# mixtape.net
KiCad netlist of a schematic drawn in EAGLE
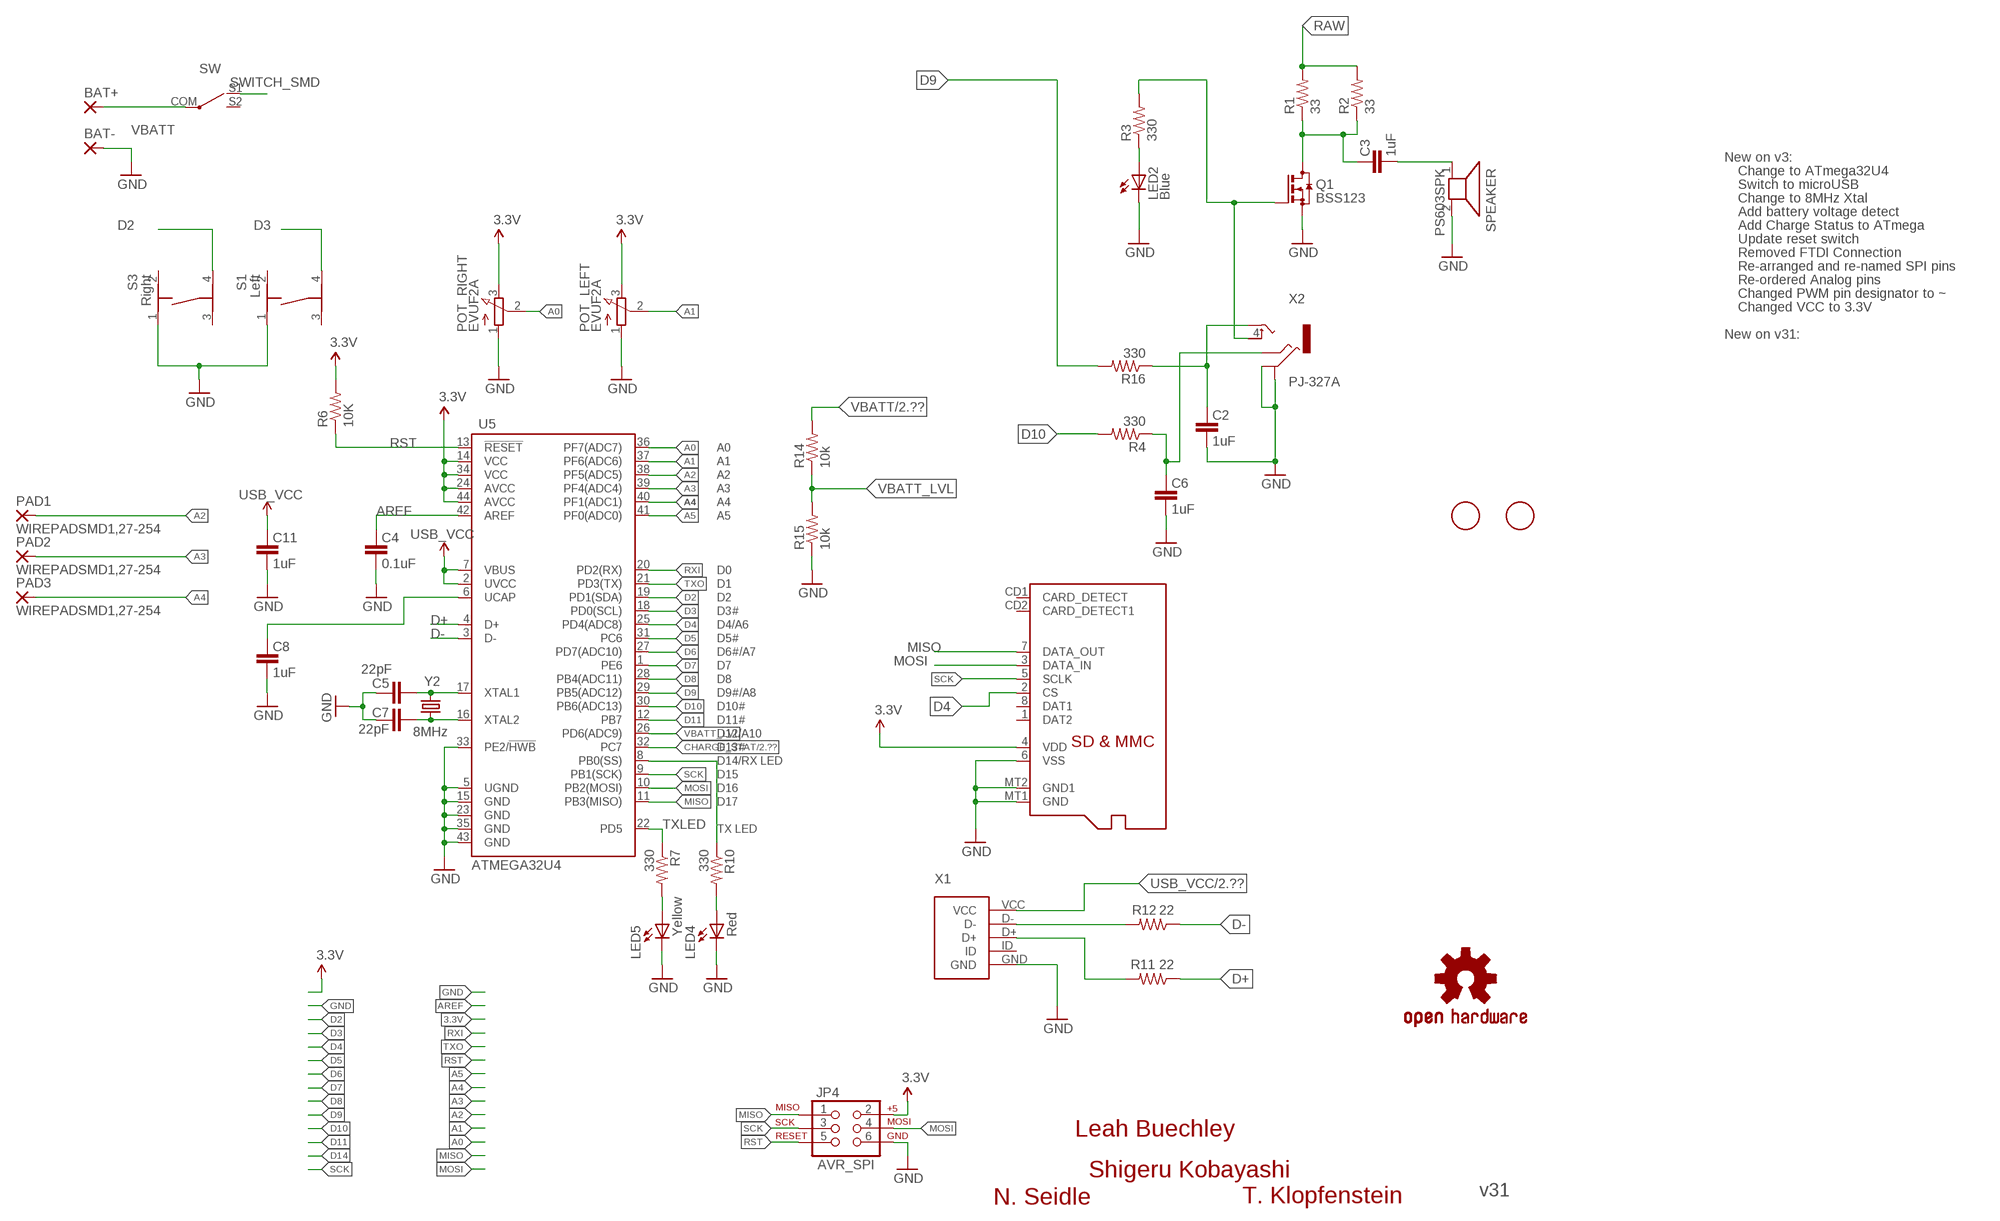
[diagram p0: schematic, sheet 1]
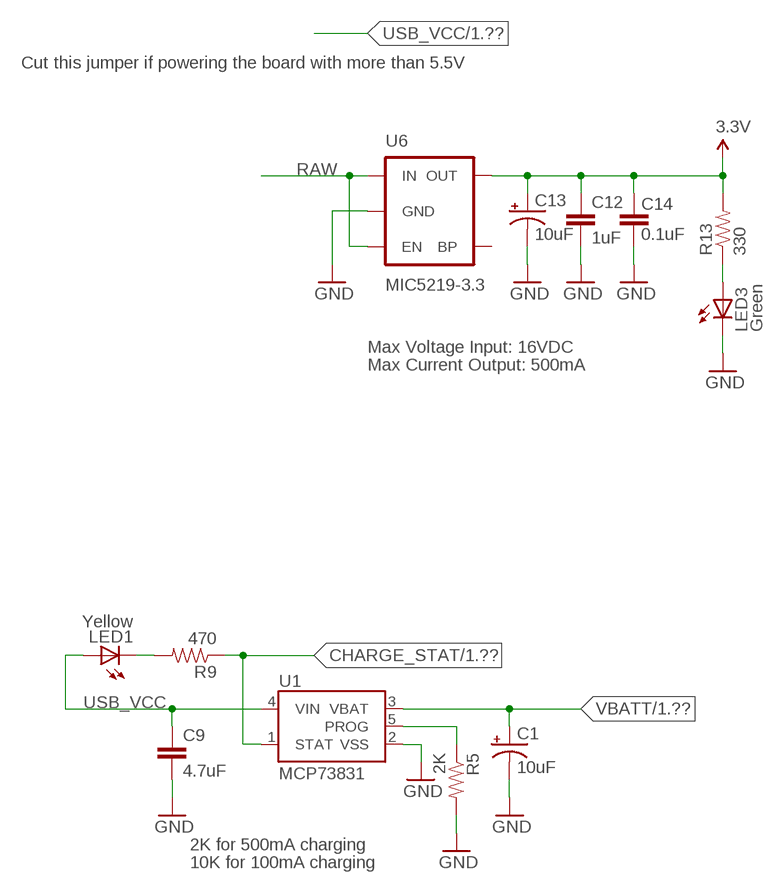
[diagram p1: schematic, sheet 2]

(export (version "E")
  (design (tool "Eeschema 10.0.6"))
  (components
    (comp (ref "C1")
      (value "10uF")
      (footprint "eagle-import:EIA3216")
      (libsource (lib "eagle-import") (part "CAP_POL1206"))
    )
    (comp (ref "C9")
      (value "4.7uF")
      (footprint "eagle-import:0603-CAP")
      (libsource (lib "eagle-import") (part "CAP0603-CAP"))
    )
    (comp (ref "C12")
      (value "1uF")
      (footprint "eagle-import:0603-CAP")
      (libsource (lib "eagle-import") (part "CAP0603-CAP"))
    )
    (comp (ref "C13")
      (value "10uF")
      (footprint "eagle-import:EIA3216")
      (libsource (lib "eagle-import") (part "CAP_POL1206"))
    )
    (comp (ref "C14")
      (value "0.1uF")
      (footprint "eagle-import:0603-CAP")
      (libsource (lib "eagle-import") (part "CAP0603-CAP"))
    )
    (comp (ref "LED1")
      (value "Yellow")
      (footprint "eagle-import:LED-0603")
      (libsource (lib "eagle-import") (part "LED0603"))
    )
    (comp (ref "LED3")
      (value "Green")
      (footprint "eagle-import:LED-0603")
      (libsource (lib "eagle-import") (part "LED0603"))
    )
    (comp (ref "R5")
      (value "2K")
      (footprint "eagle-import:0603-RES")
      (libsource (lib "eagle-import") (part "RESISTOR0603-RES"))
    )
    (comp (ref "R9")
      (value "470")
      (footprint "eagle-import:0603-RES")
      (libsource (lib "eagle-import") (part "RESISTOR0603-RES"))
    )
    (comp (ref "R13")
      (value "330")
      (footprint "eagle-import:0603-RES")
      (libsource (lib "eagle-import") (part "RESISTOR0603-RES"))
    )
    (comp (ref "U1")
      (value "MCP73831")
      (footprint "eagle-import:SOT23-5")
      (libsource (lib "eagle-import") (part "MCP73831"))
    )
    (comp (ref "U6")
      (value "MIC5219-3.3")
      (footprint "eagle-import:SOT23-5")
      (libsource (lib "eagle-import") (part "V_REG_LDOSMD"))
    )
    (comp (ref "BAT+")
      (value "SMD5")
      (footprint "eagle-import:SMD2,54-5,08")
      (libsource (lib "eagle-import") (part "SMD5"))
    )
    (comp (ref "BAT-")
      (value "SMD5")
      (footprint "eagle-import:SMD2,54-5,08")
      (libsource (lib "eagle-import") (part "SMD5"))
    )
    (comp (ref "C2")
      (value "1uF")
      (footprint "eagle-import:0603-CAP")
      (libsource (lib "eagle-import") (part "CAP0603-CAP"))
    )
    (comp (ref "C3")
      (value "1uF")
      (footprint "eagle-import:0603-CAP")
      (libsource (lib "eagle-import") (part "CAP0603-CAP"))
    )
    (comp (ref "C4")
      (value "0.1uF")
      (footprint "eagle-import:0603-CAP")
      (libsource (lib "eagle-import") (part "CAP0603-CAP"))
    )
    (comp (ref "C5")
      (value "22pF")
      (footprint "eagle-import:0603-CAP")
      (libsource (lib "eagle-import") (part "CAP0603-CAP"))
    )
    (comp (ref "C6")
      (value "1uF")
      (footprint "eagle-import:0603-CAP")
      (libsource (lib "eagle-import") (part "CAP0603-CAP"))
    )
    (comp (ref "C7")
      (value "22pF")
      (footprint "eagle-import:0603-CAP")
      (libsource (lib "eagle-import") (part "CAP0603-CAP"))
    )
    (comp (ref "C8")
      (value "1uF")
      (footprint "eagle-import:0603-CAP")
      (libsource (lib "eagle-import") (part "CAP0603-CAP"))
    )
    (comp (ref "C11")
      (value "1uF")
      (footprint "eagle-import:0603-CAP")
      (libsource (lib "eagle-import") (part "CAP0603-CAP"))
    )
    (comp (ref "JP4")
      (value "AVR_SPI")
      (footprint "eagle-import:2X3")
      (libsource (lib "eagle-import") (part "AVR_SPI_PRG_6PTH"))
    )
    (comp (ref "LED2")
      (value "Blue")
      (footprint "eagle-import:LED-0603")
      (libsource (lib "eagle-import") (part "LED0603"))
    )
    (comp (ref "LED4")
      (value "Red")
      (footprint "eagle-import:LED-0603")
      (libsource (lib "eagle-import") (part "LED0603"))
    )
    (comp (ref "LED5")
      (value "Yellow")
      (footprint "eagle-import:LED-0603")
      (libsource (lib "eagle-import") (part "LED0603"))
    )
    (comp (ref "LOGO1")
      (value "OSHW-LOGOL")
      (footprint "eagle-import:OSHW-LOGO-L")
      (libsource (lib "eagle-import") (part "OSHW-LOGOL"))
    )
    (comp (ref "PAD1")
      (value "WIREPADSMD1,27-254")
      (footprint "eagle-import:SMD1,27-2,54")
      (libsource (lib "eagle-import") (part "WIREPADSMD1,27-254"))
    )
    (comp (ref "PAD2")
      (value "WIREPADSMD1,27-254")
      (footprint "eagle-import:SMD1,27-2,54")
      (libsource (lib "eagle-import") (part "WIREPADSMD1,27-254"))
    )
    (comp (ref "PAD3")
      (value "WIREPADSMD1,27-254")
      (footprint "eagle-import:SMD1,27-2,54")
      (libsource (lib "eagle-import") (part "WIREPADSMD1,27-254"))
    )
    (comp (ref "POT_LEFT")
      (value "EVUF2A")
      (footprint "eagle-import:EVUF")
      (libsource (lib "eagle-import") (part "EVUAF2"))
    )
    (comp (ref "POT_RIGHT")
      (value "EVUF2A")
      (footprint "eagle-import:EVUF")
      (libsource (lib "eagle-import") (part "EVUAF2"))
    )
    (comp (ref "Q1")
      (value "BSS123")
      (footprint "eagle-import:SOT23")
      (libsource (lib "eagle-import") (part "BSS123"))
    )
    (comp (ref "R1")
      (value "33")
      (footprint "eagle-import:0603-RES")
      (libsource (lib "eagle-import") (part "RESISTOR0603-RES"))
    )
    (comp (ref "R2")
      (value "33")
      (footprint "eagle-import:0603-RES")
      (libsource (lib "eagle-import") (part "RESISTOR0603-RES"))
    )
    (comp (ref "R3")
      (value "330")
      (footprint "eagle-import:0603-RES")
      (libsource (lib "eagle-import") (part "RESISTOR0603-RES"))
    )
    (comp (ref "R4")
      (value "330")
      (footprint "eagle-import:0603-RES")
      (libsource (lib "eagle-import") (part "RESISTOR0603-RES"))
    )
    (comp (ref "R6")
      (value "10K")
      (footprint "eagle-import:0603-RES")
      (libsource (lib "eagle-import") (part "RESISTOR0603-RES"))
    )
    (comp (ref "R7")
      (value "330")
      (footprint "eagle-import:0603-RES")
      (libsource (lib "eagle-import") (part "RESISTOR0603-RES"))
    )
    (comp (ref "R10")
      (value "330")
      (footprint "eagle-import:0603-RES")
      (libsource (lib "eagle-import") (part "RESISTOR0603-RES"))
    )
    (comp (ref "R11")
      (value "22")
      (footprint "eagle-import:0603-RES")
      (libsource (lib "eagle-import") (part "RESISTOR0603-RES"))
    )
    (comp (ref "R12")
      (value "22")
      (footprint "eagle-import:0603-RES")
      (libsource (lib "eagle-import") (part "RESISTOR0603-RES"))
    )
    (comp (ref "R14")
      (value "10k")
      (footprint "eagle-import:0603-RES")
      (libsource (lib "eagle-import") (part "RESISTOR0603-RES"))
    )
    (comp (ref "R15")
      (value "10k")
      (footprint "eagle-import:0603-RES")
      (libsource (lib "eagle-import") (part "RESISTOR0603-RES"))
    )
    (comp (ref "R16")
      (value "330")
      (footprint "eagle-import:0603-RES")
      (libsource (lib "eagle-import") (part "RESISTOR0603-RES"))
    )
    (comp (ref "S1")
      (value "Left")
      (footprint "eagle-import:TASTER-9314_SMD")
      (libsource (lib "eagle-import") (part "TASTER-9314_SMD"))
    )
    (comp (ref "S3")
      (value "Right")
      (footprint "eagle-import:TASTER-9314_SMD")
      (libsource (lib "eagle-import") (part "TASTER-9314_SMD"))
    )
    (comp (ref "SD")
      (value "MICROSD")
      (footprint "eagle-import:MICROSD")
      (libsource (lib "eagle-import") (part "MICROSD"))
    )
    (comp (ref "SPEAKER")
      (value "PS603SPK")
      (footprint "eagle-import:PS603")
      (libsource (lib "eagle-import") (part "PS603SPK"))
    )
    (comp (ref "SW")
      (value "SWITCH_SMD")
      (footprint "eagle-import:SWITCH_SMD")
      (libsource (lib "eagle-import") (part "SWITCH_SMD"))
    )
    (comp (ref "U$1")
      (value "FIDUCIAL")
      (footprint "eagle-import:FIDUCIAL_1MM")
      (libsource (lib "eagle-import") (part "FIDUCIAL"))
    )
    (comp (ref "U$2")
      (value "FIDUCIAL")
      (footprint "eagle-import:FIDUCIAL_1MM")
      (libsource (lib "eagle-import") (part "FIDUCIAL"))
    )
    (comp (ref "U5")
      (value "ATMEGA32U4")
      (footprint "eagle-import:QFN-44-NOPAD_1_1")
      (libsource (lib "eagle-import") (part "ATMEGA32U41{colon}1"))
    )
    (comp (ref "X1")
      (value "USB_B_SMD")
      (footprint "eagle-import:USB_B_SMD")
      (libsource (lib "eagle-import") (part "USB_B_SMD"))
    )
    (comp (ref "X2")
      (value "PJ-327A")
      (footprint "eagle-import:PJ-327A")
      (libsource (lib "eagle-import") (part "PJ-327A"))
    )
    (comp (ref "Y2")
      (value "8MHz")
      (footprint "eagle-import:CRYSTAL-SMD-5X3")
      (libsource (lib "eagle-import") (part "CRYSTAL5X3"))
    )
  )
  (nets
    (net (code "1") (name "3.3V") (class "Default")
      (node (ref "C12") (pin "1") (pinfunction "1_1") (pintype "passive"))
      (node (ref "C13") (pin "A") (pinfunction "+_A") (pintype "passive"))
      (node (ref "C14") (pin "2") (pinfunction "2_2") (pintype "passive"))
      (node (ref "JP4") (pin "2") (pinfunction "2_2") (pintype "passive"))
      (node (ref "POT_LEFT") (pin "3") (pinfunction "E_3") (pintype "passive"))
      (node (ref "POT_RIGHT") (pin "3") (pinfunction "E_3") (pintype "passive"))
      (node (ref "R13") (pin "2") (pinfunction "2_2") (pintype "passive"))
      (node (ref "R6") (pin "2") (pinfunction "2_2") (pintype "passive"))
      (node (ref "SD") (pin "4") (pinfunction "VDD_4") (pintype "power_in"))
      (node (ref "U5") (pin "14") (pinfunction "VCC_14") (pintype "bidirectional"))
      (node (ref "U5") (pin "24") (pinfunction "AVCC_24") (pintype "bidirectional"))
      (node (ref "U5") (pin "34") (pinfunction "VCC_34") (pintype "bidirectional"))
      (node (ref "U5") (pin "44") (pinfunction "AVCC_44") (pintype "bidirectional"))
      (node (ref "U6") (pin "5") (pinfunction "OUT_5") (pintype "passive"))
    )
    (net (code "2") (name "A0") (class "Default")
      (node (ref "POT_RIGHT") (pin "2") (pinfunction "S_2") (pintype "passive"))
      (node (ref "U5") (pin "36") (pinfunction "PF7(ADC7)_36") (pintype "bidirectional"))
    )
    (net (code "3") (name "A1") (class "Default")
      (node (ref "POT_LEFT") (pin "2") (pinfunction "S_2") (pintype "passive"))
      (node (ref "U5") (pin "37") (pinfunction "PF6(ADC6)_37") (pintype "bidirectional"))
    )
    (net (code "4") (name "A2") (class "Default")
      (node (ref "PAD1") (pin "1") (pinfunction "P_1") (pintype "passive"))
      (node (ref "U5") (pin "38") (pinfunction "PF5(ADC5)_38") (pintype "bidirectional"))
    )
    (net (code "5") (name "A3") (class "Default")
      (node (ref "PAD2") (pin "1") (pinfunction "P_1") (pintype "passive"))
      (node (ref "U5") (pin "39") (pinfunction "PF4(ADC4)_39") (pintype "bidirectional"))
    )
    (net (code "6") (name "A4") (class "Default")
      (node (ref "PAD3") (pin "1") (pinfunction "P_1") (pintype "passive"))
      (node (ref "U5") (pin "40") (pinfunction "PF1(ADC1)_40") (pintype "bidirectional"))
    )
    (net (code "7") (name "A5") (class "Default")
      (node (ref "U5") (pin "41") (pinfunction "PF0(ADC0)_41") (pintype "bidirectional"))
    )
    (net (code "8") (name "AREF") (class "Default")
      (node (ref "C4") (pin "2") (pinfunction "2_2") (pintype "passive"))
      (node (ref "U5") (pin "42") (pinfunction "AREF_42") (pintype "bidirectional"))
    )
    (net (code "9") (name "CHARGE_STAT") (class "Default")
      (node (ref "R9") (pin "1") (pinfunction "1_1") (pintype "passive"))
      (node (ref "U1") (pin "1") (pinfunction "STAT_1") (pintype "output"))
      (node (ref "U5") (pin "32") (pinfunction "PC7_32") (pintype "bidirectional"))
    )
    (net (code "10") (name "D+") (class "Default")
      (node (ref "R11") (pin "1") (pinfunction "1_1") (pintype "passive"))
      (node (ref "U5") (pin "4") (pinfunction "D+_4") (pintype "bidirectional"))
    )
    (net (code "11") (name "D-") (class "Default")
      (node (ref "R12") (pin "1") (pinfunction "1_1") (pintype "passive"))
      (node (ref "U5") (pin "3") (pinfunction "D-_3") (pintype "bidirectional"))
    )
    (net (code "12") (name "D2") (class "Default")
      (node (ref "S3") (pin "4") (pinfunction "4_4") (pintype "passive"))
      (node (ref "U5") (pin "19") (pinfunction "PD1(SDA)_19") (pintype "bidirectional"))
    )
    (net (code "13") (name "D3") (class "Default")
      (node (ref "S1") (pin "4") (pinfunction "4_4") (pintype "passive"))
      (node (ref "U5") (pin "18") (pinfunction "PD0(SCL)_18") (pintype "bidirectional"))
    )
    (net (code "14") (name "D4") (class "Default")
      (node (ref "SD") (pin "2") (pinfunction "CS_2") (pintype "input"))
      (node (ref "U5") (pin "25") (pinfunction "PD4(ADC8)_25") (pintype "bidirectional"))
    )
    (net (code "15") (name "D5") (class "Default")
      (node (ref "U5") (pin "31") (pinfunction "PC6_31") (pintype "bidirectional"))
    )
    (net (code "16") (name "D6") (class "Default")
      (node (ref "U5") (pin "27") (pinfunction "PD7(ADC10)_27") (pintype "bidirectional"))
    )
    (net (code "17") (name "D7") (class "Default")
      (node (ref "U5") (pin "1") (pinfunction "PE6_1") (pintype "bidirectional"))
    )
    (net (code "18") (name "D8") (class "Default")
      (node (ref "U5") (pin "28") (pinfunction "PB4(ADC11)_28") (pintype "bidirectional"))
    )
    (net (code "19") (name "D9") (class "Default")
      (node (ref "R16") (pin "2") (pinfunction "2_2") (pintype "passive"))
      (node (ref "U5") (pin "29") (pinfunction "PB5(ADC12)_29") (pintype "bidirectional"))
    )
    (net (code "20") (name "D10") (class "Default")
      (node (ref "R4") (pin "2") (pinfunction "2_2") (pintype "passive"))
      (node (ref "U5") (pin "30") (pinfunction "PB6(ADC13)_30") (pintype "bidirectional"))
    )
    (net (code "21") (name "D11") (class "Default")
      (node (ref "U5") (pin "12") (pinfunction "PB7_12") (pintype "bidirectional"))
    )
    (net (code "22") (name "D14") (class "Default")
      (node (ref "R10") (pin "1") (pinfunction "1_1") (pintype "passive"))
      (node (ref "U5") (pin "8") (pinfunction "PB0(SS)_8") (pintype "bidirectional"))
    )
    (net (code "23") (name "GND") (class "Default")
      (node (ref "BAT-") (pin "1") (pinfunction "P_1") (pintype "passive"))
      (node (ref "C1") (pin "C") (pinfunction "-_C") (pintype "passive"))
      (node (ref "C11") (pin "1") (pinfunction "1_1") (pintype "passive"))
      (node (ref "C12") (pin "2") (pinfunction "2_2") (pintype "passive"))
      (node (ref "C13") (pin "C") (pinfunction "-_C") (pintype "passive"))
      (node (ref "C14") (pin "1") (pinfunction "1_1") (pintype "passive"))
      (node (ref "C2") (pin "1") (pinfunction "1_1") (pintype "passive"))
      (node (ref "C4") (pin "1") (pinfunction "1_1") (pintype "passive"))
      (node (ref "C5") (pin "2") (pinfunction "2_2") (pintype "passive"))
      (node (ref "C6") (pin "1") (pinfunction "1_1") (pintype "passive"))
      (node (ref "C7") (pin "2") (pinfunction "2_2") (pintype "passive"))
      (node (ref "C8") (pin "1") (pinfunction "1_1") (pintype "passive"))
      (node (ref "C9") (pin "2") (pinfunction "2_2") (pintype "passive"))
      (node (ref "JP4") (pin "6") (pinfunction "6_6") (pintype "passive"))
      (node (ref "LED2") (pin "C") (pinfunction "C_C") (pintype "passive"))
      (node (ref "LED3") (pin "C") (pinfunction "C_C") (pintype "passive"))
      (node (ref "LED4") (pin "C") (pinfunction "C_C") (pintype "passive"))
      (node (ref "LED5") (pin "C") (pinfunction "C_C") (pintype "passive"))
      (node (ref "POT_LEFT") (pin "1") (pinfunction "A_1") (pintype "passive"))
      (node (ref "POT_RIGHT") (pin "1") (pinfunction "A_1") (pintype "passive"))
      (node (ref "Q1") (pin "2") (pinfunction "S_2") (pintype "passive"))
      (node (ref "R15") (pin "1") (pinfunction "1_1") (pintype "passive"))
      (node (ref "R5") (pin "2") (pinfunction "2_2") (pintype "passive"))
      (node (ref "S1") (pin "1") (pinfunction "1_1") (pintype "passive"))
      (node (ref "S3") (pin "1") (pinfunction "1_1") (pintype "passive"))
      (node (ref "SD") (pin "6") (pinfunction "VSS_6") (pintype "power_in"))
      (node (ref "SD") (pin "MT1") (pinfunction "GND_MT1") (pintype "power_in"))
      (node (ref "SD") (pin "MT2") (pinfunction "GND1_MT2") (pintype "power_in"))
      (node (ref "SPEAKER") (pin "2") (pinfunction "2_2") (pintype "passive"))
      (node (ref "U1") (pin "2") (pinfunction "VSS_2") (pintype "power_in"))
      (node (ref "U5") (pin "15") (pinfunction "GND_15") (pintype "bidirectional"))
      (node (ref "U5") (pin "23") (pinfunction "GND_23") (pintype "bidirectional"))
      (node (ref "U5") (pin "33") (pinfunction "PE2/~{HWB}_33") (pintype "bidirectional"))
      (node (ref "U5") (pin "35") (pinfunction "GND_35") (pintype "bidirectional"))
      (node (ref "U5") (pin "43") (pinfunction "GND_43") (pintype "bidirectional"))
      (node (ref "U5") (pin "5") (pinfunction "UGND_5") (pintype "bidirectional"))
      (node (ref "U6") (pin "2") (pinfunction "GND_2") (pintype "input"))
      (node (ref "X1") (pin "GND") (pinfunction "GND_GND") (pintype "bidirectional"))
      (node (ref "X2") (pin "1") (pinfunction "1_1") (pintype "passive"))
      (node (ref "X2") (pin "5") (pinfunction "5_5") (pintype "passive"))
    )
    (net (code "24") (name "MISO") (class "Default")
      (node (ref "JP4") (pin "1") (pinfunction "1_1") (pintype "passive"))
      (node (ref "SD") (pin "7") (pinfunction "DATA_OUT_7") (pintype "output"))
      (node (ref "U5") (pin "11") (pinfunction "PB3(MISO)_11") (pintype "bidirectional"))
    )
    (net (code "25") (name "MOSI") (class "Default")
      (node (ref "JP4") (pin "4") (pinfunction "4_4") (pintype "passive"))
      (node (ref "SD") (pin "3") (pinfunction "DATA_IN_3") (pintype "input"))
      (node (ref "U5") (pin "10") (pinfunction "PB2(MOSI)_10") (pintype "bidirectional"))
    )
    (net (code "26") (name "Net-(C2-Pad2)") (class "Default")
      (node (ref "C2") (pin "2") (pinfunction "2_2") (pintype "passive"))
      (node (ref "R16") (pin "1") (pinfunction "1_1") (pintype "passive"))
      (node (ref "X2") (pin "2") (pinfunction "2_2") (pintype "passive"))
    )
    (net (code "27") (name "Net-(C3-Pad1)") (class "Default")
      (node (ref "C3") (pin "1") (pinfunction "1_1") (pintype "passive"))
      (node (ref "SPEAKER") (pin "1") (pinfunction "1_1") (pintype "passive"))
    )
    (net (code "28") (name "Net-(C6-Pad2)") (class "Default")
      (node (ref "C6") (pin "2") (pinfunction "2_2") (pintype "passive"))
      (node (ref "R4") (pin "1") (pinfunction "1_1") (pintype "passive"))
      (node (ref "X2") (pin "3") (pinfunction "3_3") (pintype "passive"))
    )
    (net (code "29") (name "Net-(LED1-PadC)") (class "Default")
      (node (ref "LED1") (pin "C") (pinfunction "C_C") (pintype "passive"))
      (node (ref "R9") (pin "2") (pinfunction "2_2") (pintype "passive"))
    )
    (net (code "30") (name "Net-(LED2-PadA)") (class "Default")
      (node (ref "LED2") (pin "A") (pinfunction "A_A") (pintype "passive"))
      (node (ref "R3") (pin "1") (pinfunction "1_1") (pintype "passive"))
    )
    (net (code "31") (name "Net-(LED3-PadA)") (class "Default")
      (node (ref "LED3") (pin "A") (pinfunction "A_A") (pintype "passive"))
      (node (ref "R13") (pin "1") (pinfunction "1_1") (pintype "passive"))
    )
    (net (code "32") (name "Net-(LED4-PadA)") (class "Default")
      (node (ref "LED4") (pin "A") (pinfunction "A_A") (pintype "passive"))
      (node (ref "R10") (pin "2") (pinfunction "2_2") (pintype "passive"))
    )
    (net (code "33") (name "Net-(LED5-PadA)") (class "Default")
      (node (ref "LED5") (pin "A") (pinfunction "A_A") (pintype "passive"))
      (node (ref "R7") (pin "2") (pinfunction "2_2") (pintype "passive"))
    )
    (net (code "34") (name "Net-(Q1-D)") (class "Default")
      (node (ref "C3") (pin "2") (pinfunction "2_2") (pintype "passive"))
      (node (ref "Q1") (pin "3") (pinfunction "D_3") (pintype "passive"))
      (node (ref "R1") (pin "1") (pinfunction "1_1") (pintype "passive"))
      (node (ref "R2") (pin "1") (pinfunction "1_1") (pintype "passive"))
    )
    (net (code "35") (name "Net-(Q1-G)") (class "Default")
      (node (ref "Q1") (pin "1") (pinfunction "G_1") (pintype "passive"))
      (node (ref "R3") (pin "2") (pinfunction "2_2") (pintype "passive"))
      (node (ref "X2") (pin "4") (pinfunction "4_4") (pintype "passive"))
    )
    (net (code "36") (name "Net-(R11-Pad2)") (class "Default")
      (node (ref "R11") (pin "2") (pinfunction "2_2") (pintype "passive"))
      (node (ref "X1") (pin "D+") (pinfunction "D+_D+") (pintype "bidirectional"))
    )
    (net (code "37") (name "Net-(R12-Pad2)") (class "Default")
      (node (ref "R12") (pin "2") (pinfunction "2_2") (pintype "passive"))
      (node (ref "X1") (pin "D-") (pinfunction "D-_D-") (pintype "bidirectional"))
    )
    (net (code "38") (name "Net-(U1-PROG)") (class "Default")
      (node (ref "R5") (pin "1") (pinfunction "1_1") (pintype "passive"))
      (node (ref "U1") (pin "5") (pinfunction "PROG_5") (pintype "input"))
    )
    (net (code "39") (name "Net-(U5-UCAP)") (class "Default")
      (node (ref "C8") (pin "2") (pinfunction "2_2") (pintype "passive"))
      (node (ref "U5") (pin "6") (pinfunction "UCAP_6") (pintype "bidirectional"))
    )
    (net (code "40") (name "Net-(U5-XTAL1)") (class "Default")
      (node (ref "C5") (pin "1") (pinfunction "1_1") (pintype "passive"))
      (node (ref "U5") (pin "17") (pinfunction "XTAL1_17") (pintype "bidirectional"))
      (node (ref "Y2") (pin "3") (pinfunction "2_3") (pintype "passive"))
    )
    (net (code "41") (name "Net-(U5-XTAL2)") (class "Default")
      (node (ref "C7") (pin "1") (pinfunction "1_1") (pintype "passive"))
      (node (ref "U5") (pin "16") (pinfunction "XTAL2_16") (pintype "bidirectional"))
      (node (ref "Y2") (pin "1") (pinfunction "1_1") (pintype "passive"))
    )
    (net (code "42") (name "RAW") (class "Default")
      (node (ref "R1") (pin "2") (pinfunction "2_2") (pintype "passive"))
      (node (ref "R2") (pin "2") (pinfunction "2_2") (pintype "passive"))
      (node (ref "SW") (pin "S1") (pinfunction "S1_S1") (pintype "passive"))
      (node (ref "U6") (pin "1") (pinfunction "IN_1") (pintype "input"))
      (node (ref "U6") (pin "3") (pinfunction "EN_3") (pintype "input"))
    )
    (net (code "43") (name "RST") (class "Default")
      (node (ref "JP4") (pin "5") (pinfunction "5_5") (pintype "passive"))
      (node (ref "R6") (pin "1") (pinfunction "1_1") (pintype "passive"))
      (node (ref "U5") (pin "13") (pinfunction "~{RESET}_13") (pintype "bidirectional"))
    )
    (net (code "44") (name "RXI") (class "Default")
      (node (ref "U5") (pin "20") (pinfunction "PD2(RX)_20") (pintype "bidirectional"))
    )
    (net (code "45") (name "SCK") (class "Default")
      (node (ref "JP4") (pin "3") (pinfunction "3_3") (pintype "passive"))
      (node (ref "SD") (pin "5") (pinfunction "SCLK_5") (pintype "input"))
      (node (ref "U5") (pin "9") (pinfunction "PB1(SCK)_9") (pintype "bidirectional"))
    )
    (net (code "46") (name "TXLED") (class "Default")
      (node (ref "R7") (pin "1") (pinfunction "1_1") (pintype "passive"))
      (node (ref "U5") (pin "22") (pinfunction "PD5_22") (pintype "bidirectional"))
    )
    (net (code "47") (name "TXO") (class "Default")
      (node (ref "U5") (pin "21") (pinfunction "PD3(TX)_21") (pintype "bidirectional"))
    )
    (net (code "48") (name "USB_VCC") (class "Default")
      (node (ref "C11") (pin "2") (pinfunction "2_2") (pintype "passive"))
      (node (ref "C9") (pin "1") (pinfunction "1_1") (pintype "passive"))
      (node (ref "LED1") (pin "A") (pinfunction "A_A") (pintype "passive"))
      (node (ref "U1") (pin "4") (pinfunction "VIN_4") (pintype "power_in"))
      (node (ref "U5") (pin "2") (pinfunction "UVCC_2") (pintype "bidirectional"))
      (node (ref "U5") (pin "7") (pinfunction "VBUS_7") (pintype "bidirectional"))
      (node (ref "X1") (pin "VCC") (pinfunction "VCC_VCC") (pintype "bidirectional"))
    )
    (net (code "49") (name "VBATT") (class "Default")
      (node (ref "BAT+") (pin "1") (pinfunction "P_1") (pintype "passive"))
      (node (ref "C1") (pin "A") (pinfunction "+_A") (pintype "passive"))
      (node (ref "R14") (pin "2") (pinfunction "2_2") (pintype "passive"))
      (node (ref "SW") (pin "COM") (pinfunction "COM_COM") (pintype "passive"))
      (node (ref "U1") (pin "3") (pinfunction "VBAT_3") (pintype "power_in"))
    )
    (net (code "50") (name "VBATT_LVL") (class "Default")
      (node (ref "R14") (pin "1") (pinfunction "1_1") (pintype "passive"))
      (node (ref "R15") (pin "2") (pinfunction "2_2") (pintype "passive"))
      (node (ref "U5") (pin "26") (pinfunction "PD6(ADC9)_26") (pintype "bidirectional"))
    )
    (net (code "51") (name "unconnected-(S1-Pad2)") (class "Default")
      (node (ref "S1") (pin "2") (pinfunction "2_2") (pintype "passive"))
    )
    (net (code "52") (name "unconnected-(S1-Pad3)") (class "Default")
      (node (ref "S1") (pin "3") (pinfunction "3_3") (pintype "passive"))
    )
    (net (code "53") (name "unconnected-(S3-Pad2)") (class "Default")
      (node (ref "S3") (pin "2") (pinfunction "2_2") (pintype "passive"))
    )
    (net (code "54") (name "unconnected-(S3-Pad3)") (class "Default")
      (node (ref "S3") (pin "3") (pinfunction "3_3") (pintype "passive"))
    )
    (net (code "55") (name "unconnected-(SD-CARD_DETECT-PadCD1)") (class "Default")
      (node (ref "SD") (pin "CD1") (pinfunction "CARD_DETECT_CD1") (pintype "passive"))
    )
    (net (code "56") (name "unconnected-(SD-CARD_DETECT1-PadCD2)") (class "Default")
      (node (ref "SD") (pin "CD2") (pinfunction "CARD_DETECT1_CD2") (pintype "passive"))
    )
    (net (code "57") (name "unconnected-(SD-DAT1-Pad8)") (class "Default")
      (node (ref "SD") (pin "8") (pinfunction "DAT1_8") (pintype "bidirectional"))
    )
    (net (code "58") (name "unconnected-(SD-DAT2-Pad1)") (class "Default")
      (node (ref "SD") (pin "1") (pinfunction "DAT2_1") (pintype "bidirectional"))
    )
    (net (code "59") (name "unconnected-(SW-PadS2)") (class "Default")
      (node (ref "SW") (pin "S2") (pinfunction "S2_S2") (pintype "passive"))
    )
    (net (code "60") (name "unconnected-(U6-BP-Pad4)") (class "Default")
      (node (ref "U6") (pin "4") (pinfunction "BP_4") (pintype "input"))
    )
    (net (code "61") (name "unconnected-(X1-PadID)") (class "Default")
      (node (ref "X1") (pin "ID") (pinfunction "ID_ID") (pintype "bidirectional"))
    )
  )
)
